# schematic.net
KiCad netlist of a schematic drawn in EAGLE
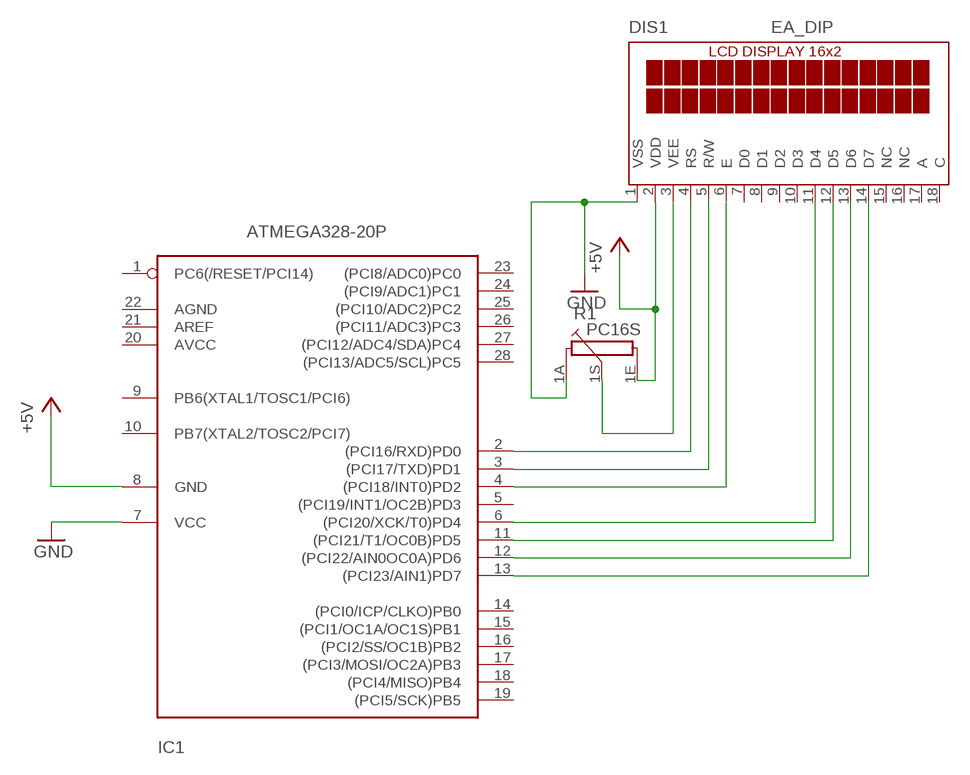
[diagram p0: schematic, sheet 1]

(export (version "E")
  (design (tool "Eeschema 10.0.6"))
  (components
    (comp (ref "DIS1")
      (value "EA_DIP")
      (footprint "eagle-import:EA_DIP")
      (libsource (lib "eagle-import") (part "EA_DIP"))
    )
    (comp (ref "IC1")
      (value "ATMEGA328-20P")
      (footprint "eagle-import:DIL28-3")
      (libsource (lib "eagle-import") (part "ATMEGA328P-20"))
    )
    (comp (ref "R1")
      (value "PC16S")
      (footprint "eagle-import:PC16S")
      (libsource (lib "eagle-import") (part "PC16S"))
    )
  )
  (nets
    (net (code "1") (name "+5V") (class "Default")
      (node (ref "DIS1") (pin "2") (pinfunction "VDD_2") (pintype "power_in"))
      (node (ref "IC1") (pin "8") (pinfunction "GND_8") (pintype "bidirectional"))
      (node (ref "R1") (pin "1E") (pinfunction "1E_1E") (pintype "passive"))
    )
    (net (code "2") (name "GND") (class "Default")
      (node (ref "DIS1") (pin "1") (pinfunction "VSS_1") (pintype "power_in"))
      (node (ref "IC1") (pin "7") (pinfunction "VCC_7") (pintype "bidirectional"))
      (node (ref "R1") (pin "1A") (pinfunction "1A_1A") (pintype "passive"))
    )
    (net (code "3") (name "Net-(DIS1-D4)") (class "Default")
      (node (ref "DIS1") (pin "11") (pinfunction "D4_11") (pintype "input"))
      (node (ref "IC1") (pin "6") (pinfunction "(PCI20/XCK/T0)PD4_6") (pintype "bidirectional"))
    )
    (net (code "4") (name "Net-(DIS1-D5)") (class "Default")
      (node (ref "DIS1") (pin "12") (pinfunction "D5_12") (pintype "input"))
      (node (ref "IC1") (pin "11") (pinfunction "(PCI21/T1/OC0B)PD5_11") (pintype "bidirectional"))
    )
    (net (code "5") (name "Net-(DIS1-D6)") (class "Default")
      (node (ref "DIS1") (pin "13") (pinfunction "D6_13") (pintype "input"))
      (node (ref "IC1") (pin "12") (pinfunction "(PCI22/AIN0OC0A)PD6_12") (pintype "bidirectional"))
    )
    (net (code "6") (name "Net-(DIS1-D7)") (class "Default")
      (node (ref "DIS1") (pin "14") (pinfunction "D7_14") (pintype "input"))
      (node (ref "IC1") (pin "13") (pinfunction "(PCI23/AIN1)PD7_13") (pintype "bidirectional"))
    )
    (net (code "7") (name "Net-(DIS1-E)") (class "Default")
      (node (ref "DIS1") (pin "6") (pinfunction "E_6") (pintype "input"))
      (node (ref "IC1") (pin "4") (pinfunction "(PCI18/INT0)PD2_4") (pintype "bidirectional"))
    )
    (net (code "8") (name "Net-(DIS1-RS)") (class "Default")
      (node (ref "DIS1") (pin "4") (pinfunction "RS_4") (pintype "input"))
      (node (ref "IC1") (pin "2") (pinfunction "(PCI16/RXD)PD0_2") (pintype "bidirectional"))
    )
    (net (code "9") (name "Net-(DIS1-R{slash}W)") (class "Default")
      (node (ref "DIS1") (pin "5") (pinfunction "R/W_5") (pintype "input"))
      (node (ref "IC1") (pin "3") (pinfunction "(PCI17/TXD)PD1_3") (pintype "bidirectional"))
    )
    (net (code "10") (name "Net-(DIS1-VEE)") (class "Default")
      (node (ref "DIS1") (pin "3") (pinfunction "VEE_3") (pintype "power_in"))
      (node (ref "R1") (pin "1S") (pinfunction "1S_1S") (pintype "passive"))
    )
    (net (code "11") (name "unconnected-(DIS1-A-Pad17)") (class "Default")
      (node (ref "DIS1") (pin "17") (pinfunction "A_17") (pintype "passive"))
    )
    (net (code "12") (name "unconnected-(DIS1-C-Pad18)") (class "Default")
      (node (ref "DIS1") (pin "18") (pinfunction "C_18") (pintype "passive"))
    )
    (net (code "13") (name "unconnected-(DIS1-D0-Pad7)") (class "Default")
      (node (ref "DIS1") (pin "7") (pinfunction "D0_7") (pintype "input"))
    )
    (net (code "14") (name "unconnected-(DIS1-D1-Pad8)") (class "Default")
      (node (ref "DIS1") (pin "8") (pinfunction "D1_8") (pintype "input"))
    )
    (net (code "15") (name "unconnected-(DIS1-D2-Pad9)") (class "Default")
      (node (ref "DIS1") (pin "9") (pinfunction "D2_9") (pintype "input"))
    )
    (net (code "16") (name "unconnected-(DIS1-D3-Pad10)") (class "Default")
      (node (ref "DIS1") (pin "10") (pinfunction "D3_10") (pintype "input"))
    )
    (net (code "17") (name "unconnected-(DIS1-NC-Pad15)") (class "Default")
      (node (ref "DIS1") (pin "15") (pinfunction "NC_15") (pintype "no_connect"))
    )
    (net (code "18") (name "unconnected-(DIS1-NC-Pad16)") (class "Default")
      (node (ref "DIS1") (pin "16") (pinfunction "NC_16") (pintype "no_connect"))
    )
    (net (code "19") (name "unconnected-(IC1-(PCI0{slash}ICP{slash}CLKO)PB0-Pad14)") (class "Default")
      (node (ref "IC1") (pin "14") (pinfunction "(PCI0/ICP/CLKO)PB0_14") (pintype "bidirectional"))
    )
    (net (code "20") (name "unconnected-(IC1-(PCI1{slash}OC1A{slash}OC1S)PB1-Pad15)") (class "Default")
      (node (ref "IC1") (pin "15") (pinfunction "(PCI1/OC1A/OC1S)PB1_15") (pintype "bidirectional"))
    )
    (net (code "21") (name "unconnected-(IC1-(PCI2{slash}SS{slash}OC1B)PB2-Pad16)") (class "Default")
      (node (ref "IC1") (pin "16") (pinfunction "(PCI2/SS/OC1B)PB2_16") (pintype "bidirectional"))
    )
    (net (code "22") (name "unconnected-(IC1-(PCI3{slash}MOSI{slash}OC2A)PB3-Pad17)") (class "Default")
      (node (ref "IC1") (pin "17") (pinfunction "(PCI3/MOSI/OC2A)PB3_17") (pintype "bidirectional"))
    )
    (net (code "23") (name "unconnected-(IC1-(PCI4{slash}MISO)PB4-Pad18)") (class "Default")
      (node (ref "IC1") (pin "18") (pinfunction "(PCI4/MISO)PB4_18") (pintype "bidirectional"))
    )
    (net (code "24") (name "unconnected-(IC1-(PCI5{slash}SCK)PB5-Pad19)") (class "Default")
      (node (ref "IC1") (pin "19") (pinfunction "(PCI5/SCK)PB5_19") (pintype "bidirectional"))
    )
    (net (code "25") (name "unconnected-(IC1-(PCI8{slash}ADC0)PC0-Pad23)") (class "Default")
      (node (ref "IC1") (pin "23") (pinfunction "(PCI8/ADC0)PC0_23") (pintype "bidirectional"))
    )
    (net (code "26") (name "unconnected-(IC1-(PCI9{slash}ADC1)PC1-Pad24)") (class "Default")
      (node (ref "IC1") (pin "24") (pinfunction "(PCI9/ADC1)PC1_24") (pintype "bidirectional"))
    )
    (net (code "27") (name "unconnected-(IC1-(PCI10{slash}ADC2)PC2-Pad25)") (class "Default")
      (node (ref "IC1") (pin "25") (pinfunction "(PCI10/ADC2)PC2_25") (pintype "bidirectional"))
    )
    (net (code "28") (name "unconnected-(IC1-(PCI11{slash}ADC3)PC3-Pad26)") (class "Default")
      (node (ref "IC1") (pin "26") (pinfunction "(PCI11/ADC3)PC3_26") (pintype "bidirectional"))
    )
    (net (code "29") (name "unconnected-(IC1-(PCI12{slash}ADC4{slash}SDA)PC4-Pad27)") (class "Default")
      (node (ref "IC1") (pin "27") (pinfunction "(PCI12/ADC4/SDA)PC4_27") (pintype "bidirectional"))
    )
    (net (code "30") (name "unconnected-(IC1-(PCI13{slash}ADC5{slash}SCL)PC5-Pad28)") (class "Default")
      (node (ref "IC1") (pin "28") (pinfunction "(PCI13/ADC5/SCL)PC5_28") (pintype "bidirectional"))
    )
    (net (code "31") (name "unconnected-(IC1-(PCI19{slash}INT1{slash}OC2B)PD3-Pad5)") (class "Default")
      (node (ref "IC1") (pin "5") (pinfunction "(PCI19/INT1/OC2B)PD3_5") (pintype "bidirectional"))
    )
    (net (code "32") (name "unconnected-(IC1-AGND-Pad22)") (class "Default")
      (node (ref "IC1") (pin "22") (pinfunction "AGND_22") (pintype "bidirectional"))
    )
    (net (code "33") (name "unconnected-(IC1-AREF-Pad21)") (class "Default")
      (node (ref "IC1") (pin "21") (pinfunction "AREF_21") (pintype "bidirectional"))
    )
    (net (code "34") (name "unconnected-(IC1-AVCC-Pad20)") (class "Default")
      (node (ref "IC1") (pin "20") (pinfunction "AVCC_20") (pintype "bidirectional"))
    )
    (net (code "35") (name "unconnected-(IC1-PB6(XTAL1{slash}TOSC1{slash}PCI6)-Pad9)") (class "Default")
      (node (ref "IC1") (pin "9") (pinfunction "PB6(XTAL1/TOSC1/PCI6)_9") (pintype "bidirectional"))
    )
    (net (code "36") (name "unconnected-(IC1-PB7(XTAL2{slash}TOSC2{slash}PCI7)-Pad10)") (class "Default")
      (node (ref "IC1") (pin "10") (pinfunction "PB7(XTAL2/TOSC2/PCI7)_10") (pintype "bidirectional"))
    )
    (net (code "37") (name "unconnected-(IC1-PC6({slash}RESET{slash}PCI14)-Pad1)") (class "Default")
      (node (ref "IC1") (pin "1") (pinfunction "PC6(/RESET/PCI14)_1") (pintype "bidirectional"))
    )
  )
)
